# DM3390_Connector_B.net
KiCad netlist of a schematic drawn in Altium Designer
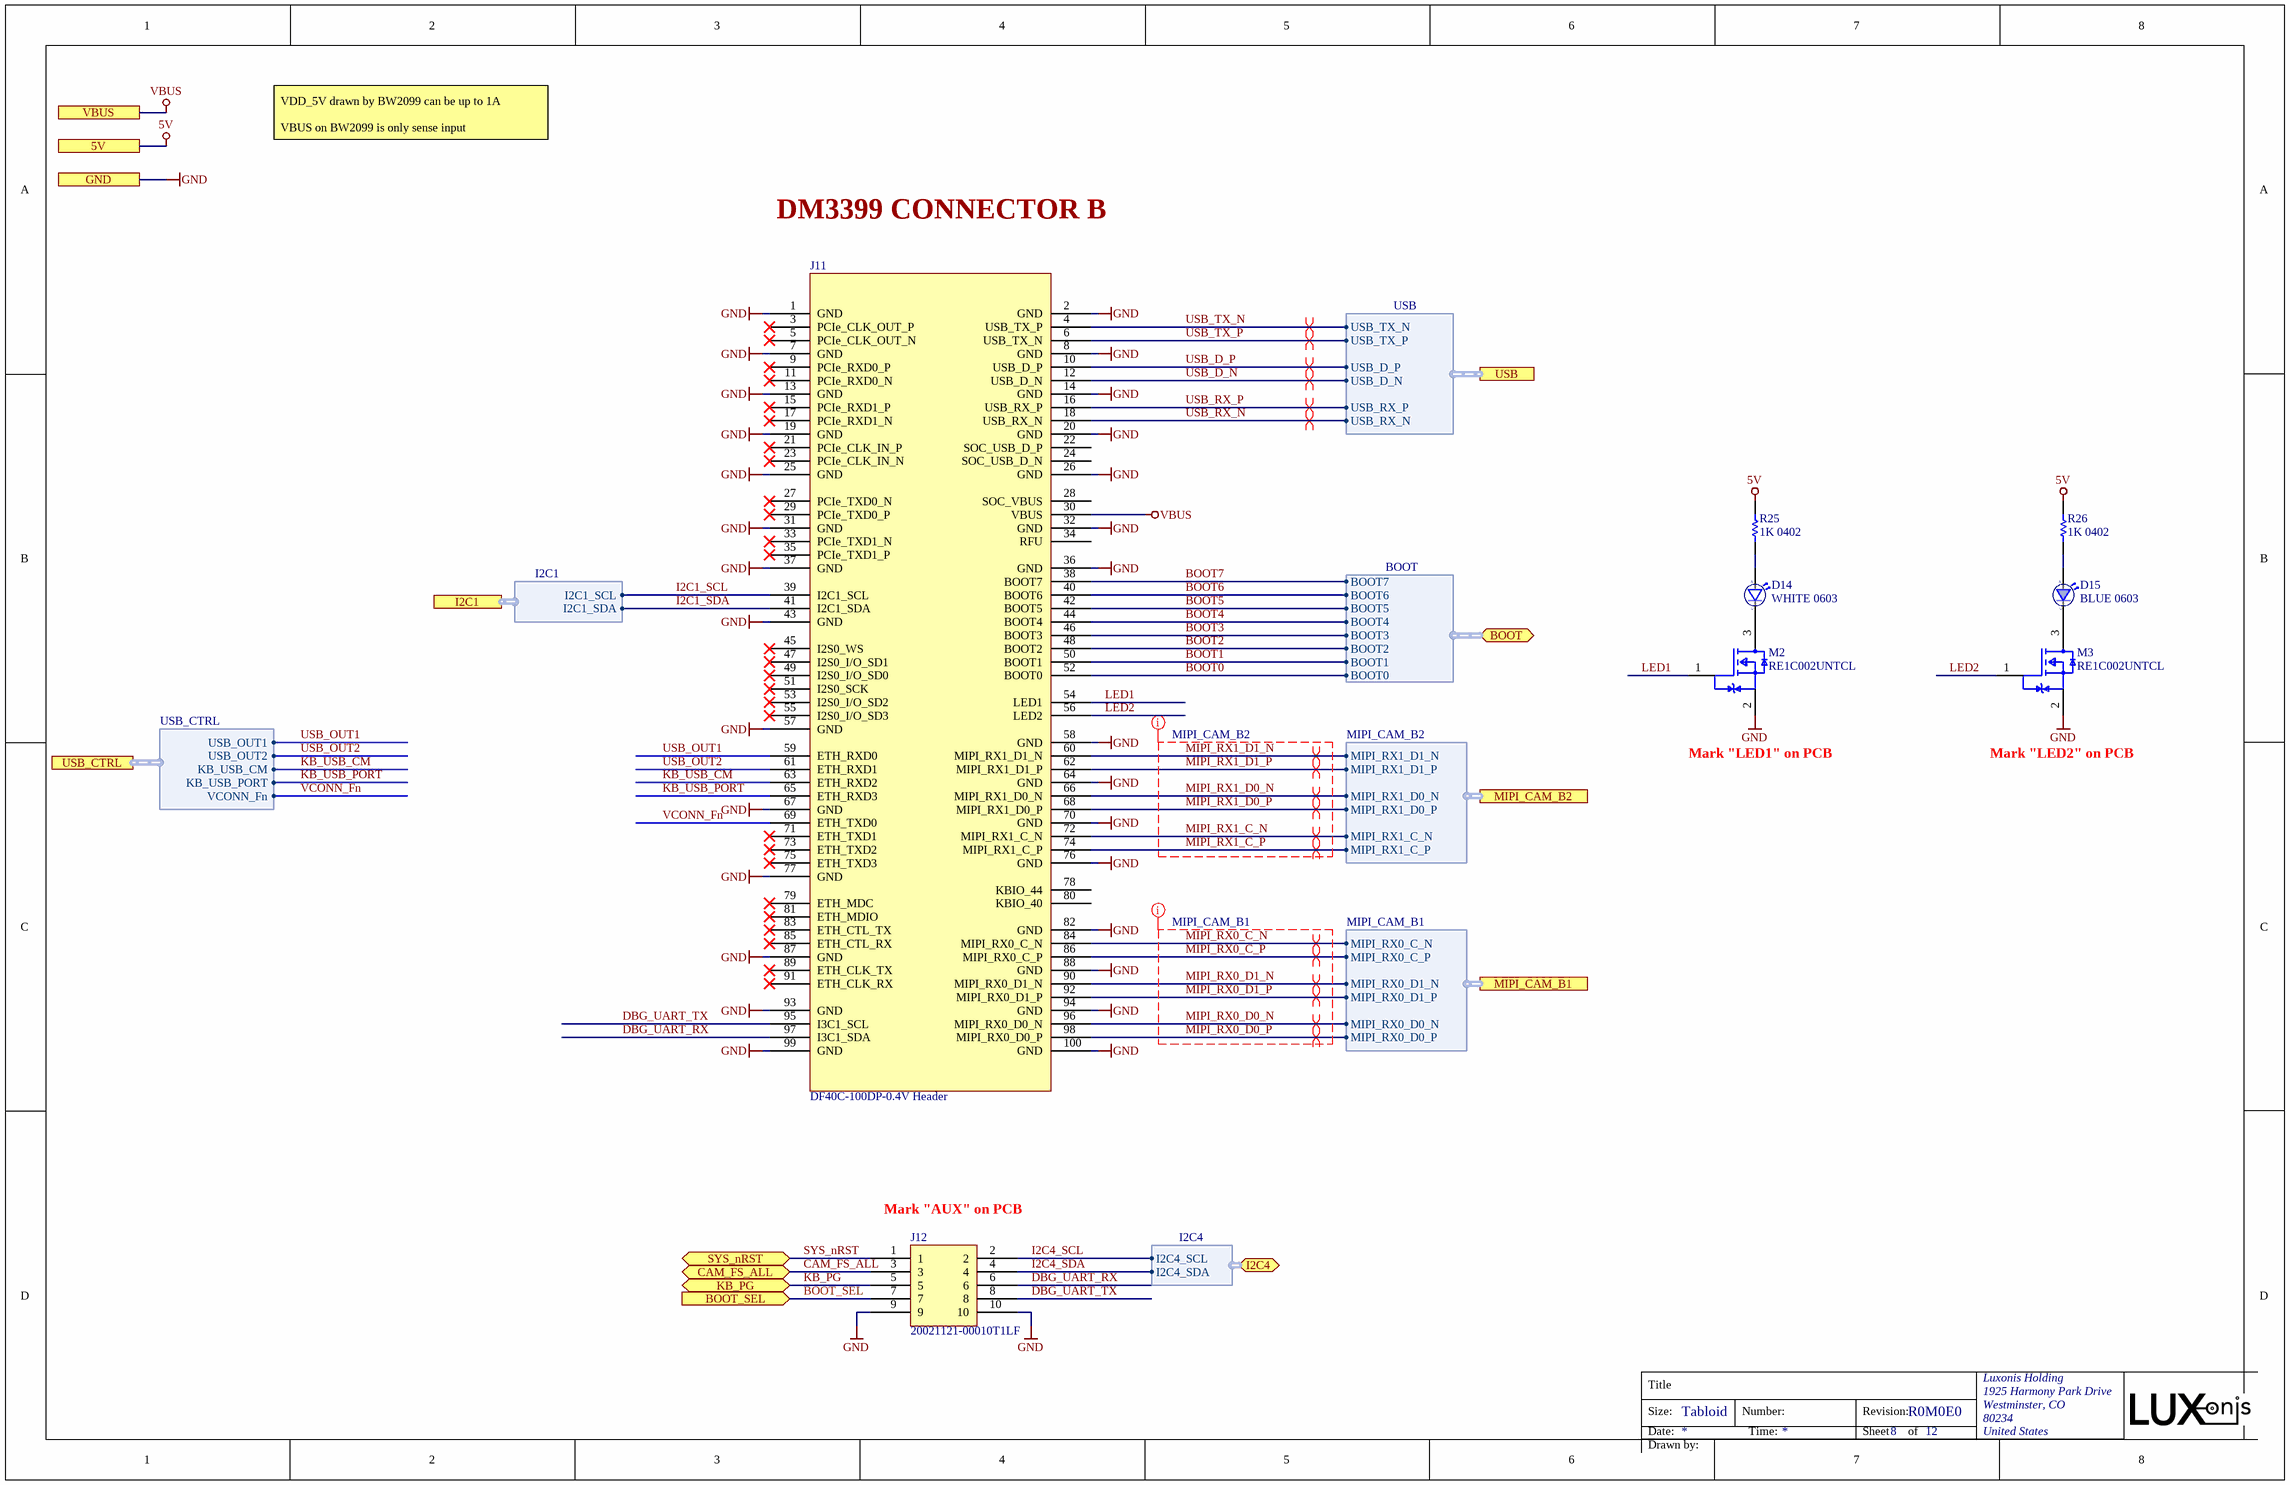
[diagram p0: DM3390_Connector_B.SchDoc]

(export (version "E")
  (design (tool "Eeschema 10.0.6"))
  (components
    (comp (ref "D14")
      (value "WHITE 0603")
      (footprint "LuxonisMaster:SML_D1xx8W")
      (description "LED Uni-Color White 2-Pin Chip 0603(1608Metric) T/R")
      (libsource (lib "LuxonisMaster") (part "SML-D12WBN1W1"))
    )
    (comp (ref "D15")
      (value "BLUE 0603")
      (footprint "LuxonisMaster:SML_D1xx8W")
      (description "LED Uni-Color Blue 2-Pin Chip 0603(1608Metric) T/R")
      (libsource (lib "LuxonisMaster") (part "SML-D12BN1WT86"))
    )
    (comp (ref "J11")
      (value "DF40C-100DP-0.4V Header")
      (footprint "LuxonisMaster:CON_B_SoM-MAX_DF40HC-3.0-100DS-0.4V_minpad")
      (description "CONN HDR 100POS 0.4MM SMD GOLD BW2099 SYMBOL")
      (fields (field (name "MFG") "Hirose"))
      (libsource (lib "LuxonisMaster") (part "DF40HC(3.0)-100DS-0.4V_OAK-SoM-MAX_B"))
    )
    (comp (ref "J12")
      (value "20021121-00010T1LF")
      (footprint "LuxonisMaster:20021121-00010T1LF")
      (description "CONN HEADER SMD 10POS 1.27MM")
      (libsource (lib "LuxonisMaster") (part "20021121-00010T1LF"))
    )
    (comp (ref "M2")
      (value "RE1C002UNTCL")
      (footprint "LuxonisMaster:RE1C002UNTCL")
      (description "MOSFET N-CH 20V 0.2A EMT3")
      (libsource (lib "LuxonisMaster") (part "RE1C002UNTCL"))
    )
    (comp (ref "M3")
      (value "RE1C002UNTCL")
      (footprint "LuxonisMaster:RE1C002UNTCL")
      (description "MOSFET N-CH 20V 0.2A EMT3")
      (libsource (lib "LuxonisMaster") (part "RE1C002UNTCL"))
    )
    (comp (ref "R25")
      (value "1K 0402")
      (footprint "RES_Altium_Vault_Generic:RESC0402(1005)_N")
      (fields (field (name "TOLERANCE") "1%"))
      (libsource (lib "LuxonisMaster") (part "RC0402FR-071KL"))
    )
    (comp (ref "R26")
      (value "1K 0402")
      (footprint "RES_Altium_Vault_Generic:RESC0402(1005)_N")
      (fields (field (name "TOLERANCE") "1%"))
      (libsource (lib "LuxonisMaster") (part "RC0402FR-071KL"))
    )
  )
  (nets
    (net (code "8") (name "/BOOT0") (class "Default")
      (node (ref "J11") (pin "52") (pinfunction "BOOT0_52") (pintype "passive"))
    )
    (net (code "9") (name "/BOOT1") (class "Default")
      (node (ref "J11") (pin "50") (pinfunction "BOOT1_50") (pintype "passive"))
    )
    (net (code "10") (name "/BOOT2") (class "Default")
      (node (ref "J11") (pin "48") (pinfunction "BOOT2_48") (pintype "passive"))
    )
    (net (code "11") (name "/BOOT3") (class "Default")
      (node (ref "J11") (pin "46") (pinfunction "BOOT3_46") (pintype "passive"))
    )
    (net (code "12") (name "/BOOT4") (class "Default")
      (node (ref "J11") (pin "44") (pinfunction "BOOT4_44") (pintype "passive"))
    )
    (net (code "13") (name "/BOOT5") (class "Default")
      (node (ref "J11") (pin "42") (pinfunction "BOOT5_42") (pintype "passive"))
    )
    (net (code "14") (name "/BOOT6") (class "Default")
      (node (ref "J11") (pin "40") (pinfunction "BOOT6_40") (pintype "passive"))
    )
    (net (code "15") (name "/BOOT7") (class "Default")
      (node (ref "J11") (pin "38") (pinfunction "BOOT7_38") (pintype "passive"))
    )
    (net (code "16") (name "/BOOT_SEL") (class "Default")
      (node (ref "J12") (pin "7") (pinfunction "7_7") (pintype "passive"))
    )
    (net (code "17") (name "/CAM_FS_ALL") (class "Default")
      (node (ref "J12") (pin "3") (pinfunction "3_3") (pintype "passive"))
    )
    (net (code "18") (name "/DBG_UART_RX") (class "Default")
      (node (ref "J11") (pin "97") (pinfunction "I3C1_SDA_97") (pintype "passive"))
      (node (ref "J12") (pin "6") (pinfunction "6_6") (pintype "passive"))
    )
    (net (code "19") (name "/DBG_UART_TX") (class "Default")
      (node (ref "J11") (pin "95") (pinfunction "I3C1_SCL_95") (pintype "passive"))
      (node (ref "J12") (pin "8") (pinfunction "8_8") (pintype "passive"))
    )
    (net (code "20") (name "/I2C1_SCL") (class "Default")
      (node (ref "J11") (pin "39") (pinfunction "I2C1_SCL_39") (pintype "passive"))
    )
    (net (code "21") (name "/I2C1_SDA") (class "Default")
      (node (ref "J11") (pin "41") (pinfunction "I2C1_SDA_41") (pintype "passive"))
    )
    (net (code "22") (name "/I2C4_SCL") (class "Default")
      (node (ref "J12") (pin "2") (pinfunction "2_2") (pintype "passive"))
    )
    (net (code "23") (name "/I2C4_SDA") (class "Default")
      (node (ref "J12") (pin "4") (pinfunction "4_4") (pintype "passive"))
    )
    (net (code "24") (name "/KB_PG") (class "Default")
      (node (ref "J12") (pin "5") (pinfunction "5_5") (pintype "passive"))
    )
    (net (code "25") (name "/KB_USB_CM") (class "Default")
      (node (ref "J11") (pin "63") (pinfunction "ETH_RXD2_63") (pintype "passive"))
    )
    (net (code "26") (name "/KB_USB_PORT") (class "Default")
      (node (ref "J11") (pin "65") (pinfunction "ETH_RXD3_65") (pintype "passive"))
    )
    (net (code "27") (name "/LED1") (class "Default")
      (node (ref "J11") (pin "54") (pinfunction "LED1_54") (pintype "passive"))
      (node (ref "M2") (pin "1") (pinfunction "Gate_1") (pintype "passive"))
    )
    (net (code "28") (name "/LED2") (class "Default")
      (node (ref "J11") (pin "56") (pinfunction "LED2_56") (pintype "passive"))
      (node (ref "M3") (pin "1") (pinfunction "Gate_1") (pintype "passive"))
    )
    (net (code "29") (name "/MIPI_RX0_C_N") (class "Default")
      (node (ref "J11") (pin "84") (pinfunction "MIPI_RX0_C_N_84") (pintype "passive"))
    )
    (net (code "30") (name "/MIPI_RX0_C_P") (class "Default")
      (node (ref "J11") (pin "86") (pinfunction "MIPI_RX0_C_P_86") (pintype "passive"))
    )
    (net (code "31") (name "/MIPI_RX0_D0_N") (class "Default")
      (node (ref "J11") (pin "96") (pinfunction "MIPI_RX0_D0_N_96") (pintype "passive"))
    )
    (net (code "32") (name "/MIPI_RX0_D0_P") (class "Default")
      (node (ref "J11") (pin "98") (pinfunction "MIPI_RX0_D0_P_98") (pintype "passive"))
    )
    (net (code "33") (name "/MIPI_RX0_D1_N") (class "Default")
      (node (ref "J11") (pin "90") (pinfunction "MIPI_RX0_D1_N_90") (pintype "passive"))
    )
    (net (code "34") (name "/MIPI_RX0_D1_P") (class "Default")
      (node (ref "J11") (pin "92") (pinfunction "MIPI_RX0_D1_P_92") (pintype "passive"))
    )
    (net (code "35") (name "/MIPI_RX1_C_N") (class "Default")
      (node (ref "J11") (pin "72") (pinfunction "MIPI_RX1_C_N_72") (pintype "passive"))
    )
    (net (code "36") (name "/MIPI_RX1_C_P") (class "Default")
      (node (ref "J11") (pin "74") (pinfunction "MIPI_RX1_C_P_74") (pintype "passive"))
    )
    (net (code "37") (name "/MIPI_RX1_D0_N") (class "Default")
      (node (ref "J11") (pin "66") (pinfunction "MIPI_RX1_D0_N_66") (pintype "passive"))
    )
    (net (code "38") (name "/MIPI_RX1_D0_P") (class "Default")
      (node (ref "J11") (pin "68") (pinfunction "MIPI_RX1_D0_P_68") (pintype "passive"))
    )
    (net (code "39") (name "/MIPI_RX1_D1_N") (class "Default")
      (node (ref "J11") (pin "60") (pinfunction "MIPI_RX1_D1_N_60") (pintype "passive"))
    )
    (net (code "40") (name "/MIPI_RX1_D1_P") (class "Default")
      (node (ref "J11") (pin "62") (pinfunction "MIPI_RX1_D1_P_62") (pintype "passive"))
    )
    (net (code "41") (name "/SYS_nRST") (class "Default")
      (node (ref "J12") (pin "1") (pinfunction "1_1") (pintype "passive"))
    )
    (net (code "42") (name "/USB_D_N") (class "Default")
      (node (ref "J11") (pin "12") (pinfunction "USB_D_N_12") (pintype "passive"))
    )
    (net (code "43") (name "/USB_D_P") (class "Default")
      (node (ref "J11") (pin "10") (pinfunction "USB_D_P_10") (pintype "passive"))
    )
    (net (code "44") (name "/USB_OUT1") (class "Default")
      (node (ref "J11") (pin "59") (pinfunction "ETH_RXD0_59") (pintype "passive"))
    )
    (net (code "45") (name "/USB_OUT2") (class "Default")
      (node (ref "J11") (pin "61") (pinfunction "ETH_RXD1_61") (pintype "passive"))
    )
    (net (code "46") (name "/USB_RX_N") (class "Default")
      (node (ref "J11") (pin "18") (pinfunction "USB_RX_N_18") (pintype "passive"))
    )
    (net (code "47") (name "/USB_RX_P") (class "Default")
      (node (ref "J11") (pin "16") (pinfunction "USB_RX_P_16") (pintype "passive"))
    )
    (net (code "48") (name "/USB_TX_N") (class "Default")
      (node (ref "J11") (pin "4") (pinfunction "USB_TX_P_4") (pintype "passive"))
    )
    (net (code "49") (name "/USB_TX_P") (class "Default")
      (node (ref "J11") (pin "6") (pinfunction "USB_TX_N_6") (pintype "passive"))
    )
    (net (code "50") (name "/VCONN_Fn") (class "Default")
      (node (ref "J11") (pin "69") (pinfunction "ETH_TXD0_69") (pintype "passive"))
    )
    (net (code "58") (name "5V") (class "Default")
      (node (ref "R25") (pin "2") (pinfunction "2_2") (pintype "passive"))
      (node (ref "R26") (pin "2") (pinfunction "2_2") (pintype "passive"))
    )
    (net (code "59") (name "GND") (class "Default")
      (node (ref "J11") (pin "1") (pinfunction "GND_1") (pintype "passive"))
      (node (ref "J11") (pin "100") (pinfunction "GND_100") (pintype "passive"))
      (node (ref "J11") (pin "13") (pinfunction "GND_13") (pintype "passive"))
      (node (ref "J11") (pin "14") (pinfunction "GND_14") (pintype "passive"))
      (node (ref "J11") (pin "19") (pinfunction "GND_19") (pintype "passive"))
      (node (ref "J11") (pin "2") (pinfunction "GND_2") (pintype "passive"))
      (node (ref "J11") (pin "20") (pinfunction "GND_20") (pintype "passive"))
      (node (ref "J11") (pin "25") (pinfunction "GND_25") (pintype "passive"))
      (node (ref "J11") (pin "26") (pinfunction "GND_26") (pintype "passive"))
      (node (ref "J11") (pin "31") (pinfunction "GND_31") (pintype "passive"))
      (node (ref "J11") (pin "32") (pinfunction "GND_32") (pintype "passive"))
      (node (ref "J11") (pin "36") (pinfunction "GND_36") (pintype "passive"))
      (node (ref "J11") (pin "37") (pinfunction "GND_37") (pintype "passive"))
      (node (ref "J11") (pin "43") (pinfunction "GND_43") (pintype "passive"))
      (node (ref "J11") (pin "57") (pinfunction "GND_57") (pintype "passive"))
      (node (ref "J11") (pin "58") (pinfunction "GND_58") (pintype "passive"))
      (node (ref "J11") (pin "64") (pinfunction "GND_64") (pintype "passive"))
      (node (ref "J11") (pin "67") (pinfunction "GND_67") (pintype "passive"))
      (node (ref "J11") (pin "7") (pinfunction "GND_7") (pintype "passive"))
      (node (ref "J11") (pin "70") (pinfunction "GND_70") (pintype "passive"))
      (node (ref "J11") (pin "76") (pinfunction "GND_76") (pintype "passive"))
      (node (ref "J11") (pin "77") (pinfunction "GND_77") (pintype "passive"))
      (node (ref "J11") (pin "8") (pinfunction "GND_8") (pintype "passive"))
      (node (ref "J11") (pin "82") (pinfunction "GND_82") (pintype "passive"))
      (node (ref "J11") (pin "87") (pinfunction "GND_87") (pintype "passive"))
      (node (ref "J11") (pin "88") (pinfunction "GND_88") (pintype "passive"))
      (node (ref "J11") (pin "93") (pinfunction "GND_93") (pintype "passive"))
      (node (ref "J11") (pin "94") (pinfunction "GND_94") (pintype "passive"))
      (node (ref "J11") (pin "99") (pinfunction "GND_99") (pintype "passive"))
      (node (ref "J12") (pin "10") (pinfunction "10_10") (pintype "passive"))
      (node (ref "J12") (pin "9") (pinfunction "9_9") (pintype "passive"))
      (node (ref "M2") (pin "2") (pinfunction "Source_2") (pintype "passive"))
      (node (ref "M3") (pin "2") (pinfunction "Source_2") (pintype "passive"))
    )
    (net (code "60") (name "Net-(D14-A)") (class "Default")
      (node (ref "D14") (pin "2") (pinfunction "A_2") (pintype "passive"))
      (node (ref "R25") (pin "1") (pinfunction "1_1") (pintype "passive"))
    )
    (net (code "61") (name "Net-(D14-C)") (class "Default")
      (node (ref "D14") (pin "1") (pinfunction "C_1") (pintype "passive"))
      (node (ref "M2") (pin "3") (pinfunction "Drain_3") (pintype "passive"))
    )
    (net (code "62") (name "Net-(D15-A)") (class "Default")
      (node (ref "D15") (pin "2") (pinfunction "A_2") (pintype "passive"))
      (node (ref "R26") (pin "1") (pinfunction "1_1") (pintype "passive"))
    )
    (net (code "63") (name "Net-(D15-C)") (class "Default")
      (node (ref "D15") (pin "1") (pinfunction "C_1") (pintype "passive"))
      (node (ref "M3") (pin "3") (pinfunction "Drain_3") (pintype "passive"))
    )
    (net (code "64") (name "VBUS") (class "Default")
      (node (ref "J11") (pin "30") (pinfunction "VBUS_30") (pintype "passive"))
    )
    (net (code "65") (name "unconnected-(J11-ETH_CLK_RX-Pad91)") (class "Default")
      (node (ref "J11") (pin "91") (pinfunction "ETH_CLK_RX_91") (pintype "passive+no_connect"))
    )
    (net (code "66") (name "unconnected-(J11-ETH_CLK_TX-Pad89)") (class "Default")
      (node (ref "J11") (pin "89") (pinfunction "ETH_CLK_TX_89") (pintype "passive+no_connect"))
    )
    (net (code "67") (name "unconnected-(J11-ETH_CTL_RX-Pad85)") (class "Default")
      (node (ref "J11") (pin "85") (pinfunction "ETH_CTL_RX_85") (pintype "passive+no_connect"))
    )
    (net (code "68") (name "unconnected-(J11-ETH_CTL_TX-Pad83)") (class "Default")
      (node (ref "J11") (pin "83") (pinfunction "ETH_CTL_TX_83") (pintype "passive+no_connect"))
    )
    (net (code "69") (name "unconnected-(J11-ETH_MDC-Pad79)") (class "Default")
      (node (ref "J11") (pin "79") (pinfunction "ETH_MDC_79") (pintype "passive+no_connect"))
    )
    (net (code "70") (name "unconnected-(J11-ETH_MDIO-Pad81)") (class "Default")
      (node (ref "J11") (pin "81") (pinfunction "ETH_MDIO_81") (pintype "passive+no_connect"))
    )
    (net (code "71") (name "unconnected-(J11-ETH_TXD1-Pad71)") (class "Default")
      (node (ref "J11") (pin "71") (pinfunction "ETH_TXD1_71") (pintype "passive+no_connect"))
    )
    (net (code "72") (name "unconnected-(J11-ETH_TXD2-Pad73)") (class "Default")
      (node (ref "J11") (pin "73") (pinfunction "ETH_TXD2_73") (pintype "passive+no_connect"))
    )
    (net (code "73") (name "unconnected-(J11-ETH_TXD3-Pad75)") (class "Default")
      (node (ref "J11") (pin "75") (pinfunction "ETH_TXD3_75") (pintype "passive+no_connect"))
    )
    (net (code "74") (name "unconnected-(J11-I2S0_I{slash}O_SD0-Pad49)") (class "Default")
      (node (ref "J11") (pin "49") (pinfunction "I2S0_I/O_SD0_49") (pintype "passive+no_connect"))
    )
    (net (code "75") (name "unconnected-(J11-I2S0_I{slash}O_SD1-Pad47)") (class "Default")
      (node (ref "J11") (pin "47") (pinfunction "I2S0_I/O_SD1_47") (pintype "passive+no_connect"))
    )
    (net (code "76") (name "unconnected-(J11-I2S0_I{slash}O_SD2-Pad53)") (class "Default")
      (node (ref "J11") (pin "53") (pinfunction "I2S0_I/O_SD2_53") (pintype "passive+no_connect"))
    )
    (net (code "77") (name "unconnected-(J11-I2S0_I{slash}O_SD3-Pad55)") (class "Default")
      (node (ref "J11") (pin "55") (pinfunction "I2S0_I/O_SD3_55") (pintype "passive+no_connect"))
    )
    (net (code "78") (name "unconnected-(J11-I2S0_SCK-Pad51)") (class "Default")
      (node (ref "J11") (pin "51") (pinfunction "I2S0_SCK_51") (pintype "passive+no_connect"))
    )
    (net (code "79") (name "unconnected-(J11-I2S0_WS-Pad45)") (class "Default")
      (node (ref "J11") (pin "45") (pinfunction "I2S0_WS_45") (pintype "passive+no_connect"))
    )
    (net (code "80") (name "unconnected-(J11-KBIO_40-Pad80)") (class "Default")
      (node (ref "J11") (pin "80") (pinfunction "KBIO_40_80") (pintype "passive"))
    )
    (net (code "81") (name "unconnected-(J11-KBIO_44-Pad78)") (class "Default")
      (node (ref "J11") (pin "78") (pinfunction "KBIO_44_78") (pintype "passive"))
    )
    (net (code "82") (name "unconnected-(J11-PCIe_CLK_IN_N-Pad23)") (class "Default")
      (node (ref "J11") (pin "23") (pinfunction "PCIe_CLK_IN_N_23") (pintype "passive+no_connect"))
    )
    (net (code "83") (name "unconnected-(J11-PCIe_CLK_IN_P-Pad21)") (class "Default")
      (node (ref "J11") (pin "21") (pinfunction "PCIe_CLK_IN_P_21") (pintype "passive+no_connect"))
    )
    (net (code "84") (name "unconnected-(J11-PCIe_CLK_OUT_N-Pad5)") (class "Default")
      (node (ref "J11") (pin "5") (pinfunction "PCIe_CLK_OUT_N_5") (pintype "passive+no_connect"))
    )
    (net (code "85") (name "unconnected-(J11-PCIe_CLK_OUT_P-Pad3)") (class "Default")
      (node (ref "J11") (pin "3") (pinfunction "PCIe_CLK_OUT_P_3") (pintype "passive+no_connect"))
    )
    (net (code "86") (name "unconnected-(J11-PCIe_RXD0_N-Pad11)") (class "Default")
      (node (ref "J11") (pin "11") (pinfunction "PCIe_RXD0_N_11") (pintype "passive+no_connect"))
    )
    (net (code "87") (name "unconnected-(J11-PCIe_RXD0_P-Pad9)") (class "Default")
      (node (ref "J11") (pin "9") (pinfunction "PCIe_RXD0_P_9") (pintype "passive+no_connect"))
    )
    (net (code "88") (name "unconnected-(J11-PCIe_RXD1_N-Pad17)") (class "Default")
      (node (ref "J11") (pin "17") (pinfunction "PCIe_RXD1_N_17") (pintype "passive+no_connect"))
    )
    (net (code "89") (name "unconnected-(J11-PCIe_RXD1_P-Pad15)") (class "Default")
      (node (ref "J11") (pin "15") (pinfunction "PCIe_RXD1_P_15") (pintype "passive+no_connect"))
    )
    (net (code "90") (name "unconnected-(J11-PCIe_TXD0_N-Pad27)") (class "Default")
      (node (ref "J11") (pin "27") (pinfunction "PCIe_TXD0_N_27") (pintype "passive+no_connect"))
    )
    (net (code "91") (name "unconnected-(J11-PCIe_TXD0_P-Pad29)") (class "Default")
      (node (ref "J11") (pin "29") (pinfunction "PCIe_TXD0_P_29") (pintype "passive+no_connect"))
    )
    (net (code "92") (name "unconnected-(J11-PCIe_TXD1_N-Pad33)") (class "Default")
      (node (ref "J11") (pin "33") (pinfunction "PCIe_TXD1_N_33") (pintype "passive+no_connect"))
    )
    (net (code "93") (name "unconnected-(J11-PCIe_TXD1_P-Pad35)") (class "Default")
      (node (ref "J11") (pin "35") (pinfunction "PCIe_TXD1_P_35") (pintype "passive+no_connect"))
    )
    (net (code "94") (name "unconnected-(J11-RFU-Pad34)") (class "Default")
      (node (ref "J11") (pin "34") (pinfunction "RFU_34") (pintype "passive"))
    )
    (net (code "95") (name "unconnected-(J11-SOC_USB_D_N-Pad24)") (class "Default")
      (node (ref "J11") (pin "24") (pinfunction "SOC_USB_D_N_24") (pintype "passive"))
    )
    (net (code "96") (name "unconnected-(J11-SOC_USB_D_P-Pad22)") (class "Default")
      (node (ref "J11") (pin "22") (pinfunction "SOC_USB_D_P_22") (pintype "passive"))
    )
    (net (code "97") (name "unconnected-(J11-SOC_VBUS-Pad28)") (class "Default")
      (node (ref "J11") (pin "28") (pinfunction "SOC_VBUS_28") (pintype "passive"))
    )
  )
)
